# Banks_13_14.net
KiCad netlist of a schematic drawn in Altium Designer
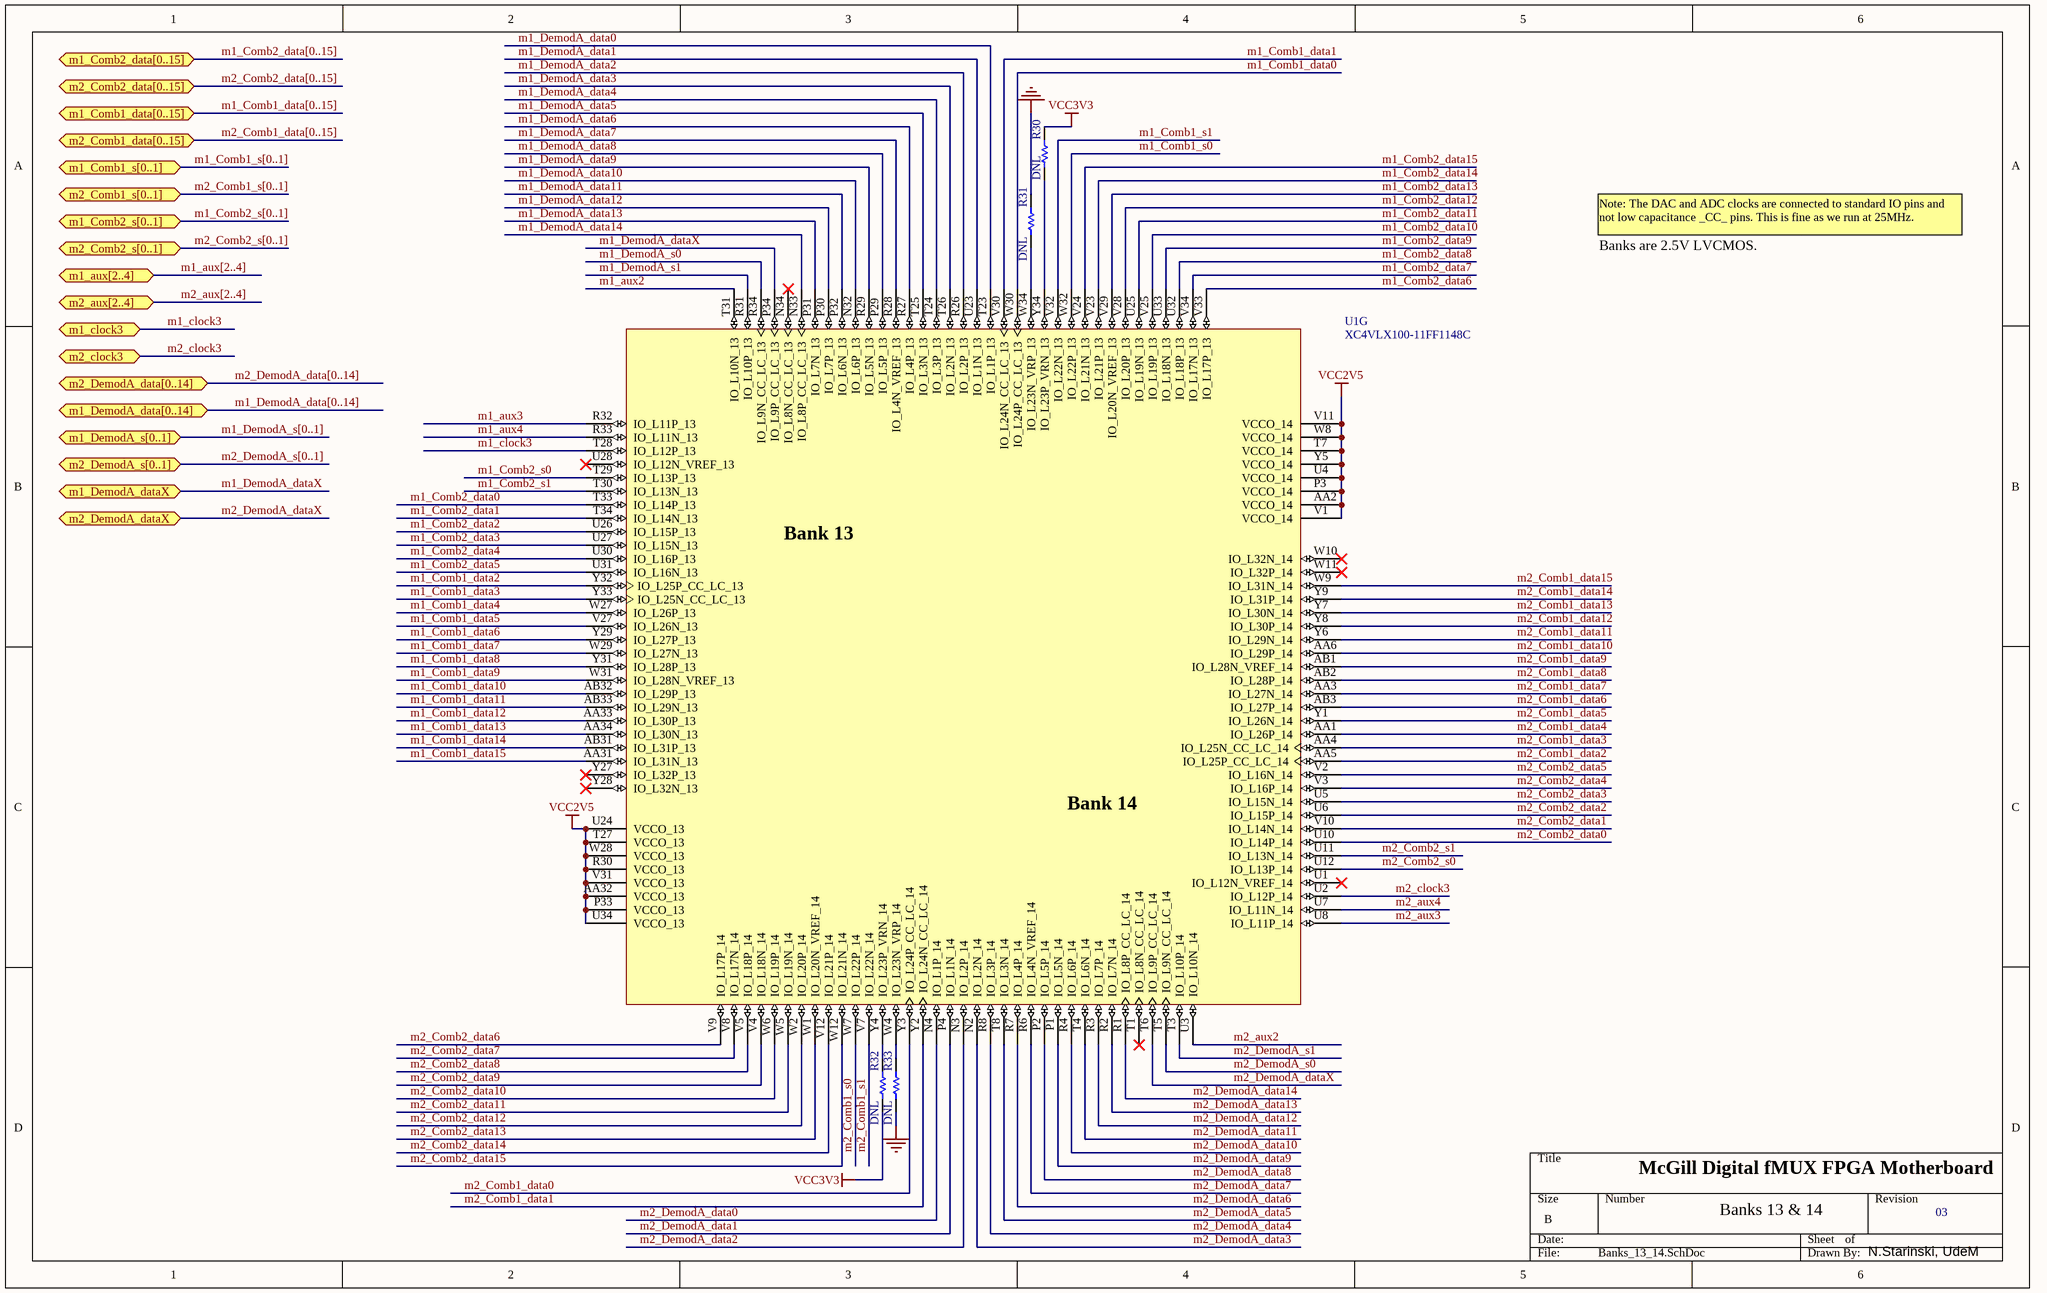
[diagram p0: Banks_13_14.SchDoc]

(export (version "E")
  (design (tool "Eeschema 10.0.6"))
  (components
    (comp (ref "R30")
      (value "DNL")
      (footprint "CR1608-0603")
      (description "Semiconductor Resistor")
      (fields (field (name "PUBLISHER") "Altium Limited"))
      (libsource (lib "Miscellaneous Devices") (part "Res Semi"))
    )
    (comp (ref "R31")
      (value "DNL")
      (footprint "CR1608-0603")
      (description "Semiconductor Resistor")
      (fields (field (name "PUBLISHER") "Altium Limited"))
      (libsource (lib "Miscellaneous Devices") (part "Res Semi"))
    )
    (comp (ref "R32")
      (value "DNL")
      (footprint "CR1608-0603")
      (description "Semiconductor Resistor")
      (fields (field (name "PUBLISHER") "Altium Limited"))
      (libsource (lib "Miscellaneous Devices") (part "Res Semi"))
    )
    (comp (ref "R33")
      (value "DNL")
      (footprint "CR1608-0603")
      (description "Semiconductor Resistor")
      (fields (field (name "PUBLISHER") "Altium Limited"))
      (libsource (lib "Miscellaneous Devices") (part "Res Semi"))
    )
    (comp (ref "U1")
      (value "XC4VLX100-11FF1148C")
      (footprint "FF1148")
      (description "Xilinx Virtex-4 LX Platform FPGA, 1148-Ball FFBGA, Speed Grade 11, 768 User I/Os, Commercial Grade")
      (fields (field (name "PUBLISHER") "Altium Limited"))
      (libsource (lib "Xilinx Virtex-4") (part "XC4VLX100-11FF1148C"))
    )
  )
  (nets
    (net (code "1") (name "/m1_Comb1_data0") (class "Default")
      (node (ref "U1") (pin "W30") (pinfunction "IO_L24P_CC_LC_13_W30") (pintype "bidirectional"))
    )
    (net (code "2") (name "/m1_Comb1_data1") (class "Default")
      (node (ref "U1") (pin "V30") (pinfunction "IO_L24N_CC_LC_13_V30") (pintype "bidirectional"))
    )
    (net (code "3") (name "/m1_Comb1_data2") (class "Default")
      (node (ref "U1") (pin "Y32") (pinfunction "IO_L25P_CC_LC_13_Y32") (pintype "bidirectional"))
    )
    (net (code "4") (name "/m1_Comb1_data3") (class "Default")
      (node (ref "U1") (pin "Y33") (pinfunction "IO_L25N_CC_LC_13_Y33") (pintype "bidirectional"))
    )
    (net (code "5") (name "/m1_Comb1_data4") (class "Default")
      (node (ref "U1") (pin "W27") (pinfunction "IO_L26P_13_W27") (pintype "bidirectional"))
    )
    (net (code "6") (name "/m1_Comb1_data5") (class "Default")
      (node (ref "U1") (pin "V27") (pinfunction "IO_L26N_13_V27") (pintype "bidirectional"))
    )
    (net (code "7") (name "/m1_Comb1_data6") (class "Default")
      (node (ref "U1") (pin "Y29") (pinfunction "IO_L27P_13_Y29") (pintype "bidirectional"))
    )
    (net (code "8") (name "/m1_Comb1_data7") (class "Default")
      (node (ref "U1") (pin "W29") (pinfunction "IO_L27N_13_W29") (pintype "bidirectional"))
    )
    (net (code "9") (name "/m1_Comb1_data8") (class "Default")
      (node (ref "U1") (pin "Y31") (pinfunction "IO_L28P_13_Y31") (pintype "bidirectional"))
    )
    (net (code "10") (name "/m1_Comb1_data9") (class "Default")
      (node (ref "U1") (pin "W31") (pinfunction "IO_L28N_VREF_13_W31") (pintype "bidirectional"))
    )
    (net (code "11") (name "/m1_Comb1_data10") (class "Default")
      (node (ref "U1") (pin "AB32") (pinfunction "IO_L29P_13_AB32") (pintype "bidirectional"))
    )
    (net (code "12") (name "/m1_Comb1_data11") (class "Default")
      (node (ref "U1") (pin "AB33") (pinfunction "IO_L29N_13_AB33") (pintype "bidirectional"))
    )
    (net (code "13") (name "/m1_Comb1_data12") (class "Default")
      (node (ref "U1") (pin "AA33") (pinfunction "IO_L30P_13_AA33") (pintype "bidirectional"))
    )
    (net (code "14") (name "/m1_Comb1_data13") (class "Default")
      (node (ref "U1") (pin "AA34") (pinfunction "IO_L30N_13_AA34") (pintype "bidirectional"))
    )
    (net (code "15") (name "/m1_Comb1_data14") (class "Default")
      (node (ref "U1") (pin "AB31") (pinfunction "IO_L31P_13_AB31") (pintype "bidirectional"))
    )
    (net (code "16") (name "/m1_Comb1_data15") (class "Default")
      (node (ref "U1") (pin "AA31") (pinfunction "IO_L31N_13_AA31") (pintype "bidirectional"))
    )
    (net (code "18") (name "/m1_Comb1_s0") (class "Default")
      (node (ref "U1") (pin "W32") (pinfunction "IO_L22P_13_W32") (pintype "bidirectional"))
    )
    (net (code "19") (name "/m1_Comb1_s1") (class "Default")
      (node (ref "U1") (pin "V32") (pinfunction "IO_L22N_13_V32") (pintype "bidirectional"))
    )
    (net (code "21") (name "/m1_Comb2_data0") (class "Default")
      (node (ref "U1") (pin "T33") (pinfunction "IO_L14P_13_T33") (pintype "bidirectional"))
    )
    (net (code "22") (name "/m1_Comb2_data1") (class "Default")
      (node (ref "U1") (pin "T34") (pinfunction "IO_L14N_13_T34") (pintype "bidirectional"))
    )
    (net (code "23") (name "/m1_Comb2_data2") (class "Default")
      (node (ref "U1") (pin "U26") (pinfunction "IO_L15P_13_U26") (pintype "bidirectional"))
    )
    (net (code "24") (name "/m1_Comb2_data3") (class "Default")
      (node (ref "U1") (pin "U27") (pinfunction "IO_L15N_13_U27") (pintype "bidirectional"))
    )
    (net (code "25") (name "/m1_Comb2_data4") (class "Default")
      (node (ref "U1") (pin "U30") (pinfunction "IO_L16P_13_U30") (pintype "bidirectional"))
    )
    (net (code "26") (name "/m1_Comb2_data5") (class "Default")
      (node (ref "U1") (pin "U31") (pinfunction "IO_L16N_13_U31") (pintype "bidirectional"))
    )
    (net (code "27") (name "/m1_Comb2_data6") (class "Default")
      (node (ref "U1") (pin "V33") (pinfunction "IO_L17P_13_V33") (pintype "bidirectional"))
    )
    (net (code "28") (name "/m1_Comb2_data7") (class "Default")
      (node (ref "U1") (pin "V34") (pinfunction "IO_L17N_13_V34") (pintype "bidirectional"))
    )
    (net (code "29") (name "/m1_Comb2_data8") (class "Default")
      (node (ref "U1") (pin "U32") (pinfunction "IO_L18P_13_U32") (pintype "bidirectional"))
    )
    (net (code "30") (name "/m1_Comb2_data9") (class "Default")
      (node (ref "U1") (pin "U33") (pinfunction "IO_L18N_13_U33") (pintype "bidirectional"))
    )
    (net (code "31") (name "/m1_Comb2_data10") (class "Default")
      (node (ref "U1") (pin "V25") (pinfunction "IO_L19P_13_V25") (pintype "bidirectional"))
    )
    (net (code "32") (name "/m1_Comb2_data11") (class "Default")
      (node (ref "U1") (pin "U25") (pinfunction "IO_L19N_13_U25") (pintype "bidirectional"))
    )
    (net (code "33") (name "/m1_Comb2_data12") (class "Default")
      (node (ref "U1") (pin "V28") (pinfunction "IO_L20P_13_V28") (pintype "bidirectional"))
    )
    (net (code "34") (name "/m1_Comb2_data13") (class "Default")
      (node (ref "U1") (pin "V29") (pinfunction "IO_L20N_VREF_13_V29") (pintype "bidirectional"))
    )
    (net (code "35") (name "/m1_Comb2_data14") (class "Default")
      (node (ref "U1") (pin "V23") (pinfunction "IO_L21P_13_V23") (pintype "bidirectional"))
    )
    (net (code "36") (name "/m1_Comb2_data15") (class "Default")
      (node (ref "U1") (pin "V24") (pinfunction "IO_L21N_13_V24") (pintype "bidirectional"))
    )
    (net (code "38") (name "/m1_Comb2_s0") (class "Default")
      (node (ref "U1") (pin "T29") (pinfunction "IO_L13P_13_T29") (pintype "bidirectional"))
    )
    (net (code "39") (name "/m1_Comb2_s1") (class "Default")
      (node (ref "U1") (pin "T30") (pinfunction "IO_L13N_13_T30") (pintype "bidirectional"))
    )
    (net (code "41") (name "/m1_DemodA_data0") (class "Default")
      (node (ref "U1") (pin "T23") (pinfunction "IO_L1P_13_T23") (pintype "bidirectional"))
    )
    (net (code "42") (name "/m1_DemodA_data1") (class "Default")
      (node (ref "U1") (pin "U23") (pinfunction "IO_L1N_13_U23") (pintype "bidirectional"))
    )
    (net (code "43") (name "/m1_DemodA_data2") (class "Default")
      (node (ref "U1") (pin "R26") (pinfunction "IO_L2P_13_R26") (pintype "bidirectional"))
    )
    (net (code "44") (name "/m1_DemodA_data3") (class "Default")
      (node (ref "U1") (pin "T26") (pinfunction "IO_L2N_13_T26") (pintype "bidirectional"))
    )
    (net (code "45") (name "/m1_DemodA_data4") (class "Default")
      (node (ref "U1") (pin "T24") (pinfunction "IO_L3P_13_T24") (pintype "bidirectional"))
    )
    (net (code "46") (name "/m1_DemodA_data5") (class "Default")
      (node (ref "U1") (pin "T25") (pinfunction "IO_L3N_13_T25") (pintype "bidirectional"))
    )
    (net (code "47") (name "/m1_DemodA_data6") (class "Default")
      (node (ref "U1") (pin "R27") (pinfunction "IO_L4P_13_R27") (pintype "bidirectional"))
    )
    (net (code "48") (name "/m1_DemodA_data7") (class "Default")
      (node (ref "U1") (pin "R28") (pinfunction "IO_L4N_VREF_13_R28") (pintype "bidirectional"))
    )
    (net (code "49") (name "/m1_DemodA_data8") (class "Default")
      (node (ref "U1") (pin "P29") (pinfunction "IO_L5P_13_P29") (pintype "bidirectional"))
    )
    (net (code "50") (name "/m1_DemodA_data9") (class "Default")
      (node (ref "U1") (pin "R29") (pinfunction "IO_L5N_13_R29") (pintype "bidirectional"))
    )
    (net (code "51") (name "/m1_DemodA_data10") (class "Default")
      (node (ref "U1") (pin "N32") (pinfunction "IO_L6P_13_N32") (pintype "bidirectional"))
    )
    (net (code "52") (name "/m1_DemodA_data11") (class "Default")
      (node (ref "U1") (pin "P32") (pinfunction "IO_L6N_13_P32") (pintype "bidirectional"))
    )
    (net (code "53") (name "/m1_DemodA_data12") (class "Default")
      (node (ref "U1") (pin "P30") (pinfunction "IO_L7P_13_P30") (pintype "bidirectional"))
    )
    (net (code "54") (name "/m1_DemodA_data13") (class "Default")
      (node (ref "U1") (pin "P31") (pinfunction "IO_L7N_13_P31") (pintype "bidirectional"))
    )
    (net (code "55") (name "/m1_DemodA_data14") (class "Default")
      (node (ref "U1") (pin "N33") (pinfunction "IO_L8P_CC_LC_13_N33") (pintype "bidirectional"))
    )
    (net (code "56") (name "/m1_DemodA_dataX") (class "Default")
      (node (ref "U1") (pin "P34") (pinfunction "IO_L9P_CC_LC_13_P34") (pintype "bidirectional"))
    )
    (net (code "58") (name "/m1_DemodA_s0") (class "Default")
      (node (ref "U1") (pin "R34") (pinfunction "IO_L9N_CC_LC_13_R34") (pintype "bidirectional"))
    )
    (net (code "59") (name "/m1_DemodA_s1") (class "Default")
      (node (ref "U1") (pin "R31") (pinfunction "IO_L10P_13_R31") (pintype "bidirectional"))
    )
    (net (code "61") (name "/m1_aux2") (class "Default")
      (node (ref "U1") (pin "T31") (pinfunction "IO_L10N_13_T31") (pintype "bidirectional"))
    )
    (net (code "62") (name "/m1_aux3") (class "Default")
      (node (ref "U1") (pin "R32") (pinfunction "IO_L11P_13_R32") (pintype "bidirectional"))
    )
    (net (code "63") (name "/m1_aux4") (class "Default")
      (node (ref "U1") (pin "R33") (pinfunction "IO_L11N_13_R33") (pintype "bidirectional"))
    )
    (net (code "65") (name "/m1_clock3") (class "Default")
      (node (ref "U1") (pin "T28") (pinfunction "IO_L12P_13_T28") (pintype "bidirectional"))
    )
    (net (code "66") (name "/m2_Comb1_data0") (class "Default")
      (node (ref "U1") (pin "Y3") (pinfunction "IO_L24P_CC_LC_14_Y3") (pintype "bidirectional"))
    )
    (net (code "67") (name "/m2_Comb1_data1") (class "Default")
      (node (ref "U1") (pin "Y2") (pinfunction "IO_L24N_CC_LC_14_Y2") (pintype "bidirectional"))
    )
    (net (code "68") (name "/m2_Comb1_data2") (class "Default")
      (node (ref "U1") (pin "AA5") (pinfunction "IO_L25P_CC_LC_14_AA5") (pintype "bidirectional"))
    )
    (net (code "69") (name "/m2_Comb1_data3") (class "Default")
      (node (ref "U1") (pin "AA4") (pinfunction "IO_L25N_CC_LC_14_AA4") (pintype "bidirectional"))
    )
    (net (code "70") (name "/m2_Comb1_data4") (class "Default")
      (node (ref "U1") (pin "AA1") (pinfunction "IO_L26P_14_AA1") (pintype "bidirectional"))
    )
    (net (code "71") (name "/m2_Comb1_data5") (class "Default")
      (node (ref "U1") (pin "Y1") (pinfunction "IO_L26N_14_Y1") (pintype "bidirectional"))
    )
    (net (code "72") (name "/m2_Comb1_data6") (class "Default")
      (node (ref "U1") (pin "AB3") (pinfunction "IO_L27P_14_AB3") (pintype "bidirectional"))
    )
    (net (code "73") (name "/m2_Comb1_data7") (class "Default")
      (node (ref "U1") (pin "AA3") (pinfunction "IO_L27N_14_AA3") (pintype "bidirectional"))
    )
    (net (code "74") (name "/m2_Comb1_data8") (class "Default")
      (node (ref "U1") (pin "AB2") (pinfunction "IO_L28P_14_AB2") (pintype "bidirectional"))
    )
    (net (code "75") (name "/m2_Comb1_data9") (class "Default")
      (node (ref "U1") (pin "AB1") (pinfunction "IO_L28N_VREF_14_AB1") (pintype "bidirectional"))
    )
    (net (code "76") (name "/m2_Comb1_data10") (class "Default")
      (node (ref "U1") (pin "AA6") (pinfunction "IO_L29P_14_AA6") (pintype "bidirectional"))
    )
    (net (code "77") (name "/m2_Comb1_data11") (class "Default")
      (node (ref "U1") (pin "Y6") (pinfunction "IO_L29N_14_Y6") (pintype "bidirectional"))
    )
    (net (code "78") (name "/m2_Comb1_data12") (class "Default")
      (node (ref "U1") (pin "Y8") (pinfunction "IO_L30P_14_Y8") (pintype "bidirectional"))
    )
    (net (code "79") (name "/m2_Comb1_data13") (class "Default")
      (node (ref "U1") (pin "Y7") (pinfunction "IO_L30N_14_Y7") (pintype "bidirectional"))
    )
    (net (code "80") (name "/m2_Comb1_data14") (class "Default")
      (node (ref "U1") (pin "Y9") (pinfunction "IO_L31P_14_Y9") (pintype "bidirectional"))
    )
    (net (code "81") (name "/m2_Comb1_data15") (class "Default")
      (node (ref "U1") (pin "W9") (pinfunction "IO_L31N_14_W9") (pintype "bidirectional"))
    )
    (net (code "83") (name "/m2_Comb1_s0") (class "Default")
      (node (ref "U1") (pin "W7") (pinfunction "IO_L22P_14_W7") (pintype "bidirectional"))
    )
    (net (code "84") (name "/m2_Comb1_s1") (class "Default")
      (node (ref "U1") (pin "V7") (pinfunction "IO_L22N_14_V7") (pintype "bidirectional"))
    )
    (net (code "86") (name "/m2_Comb2_data0") (class "Default")
      (node (ref "U1") (pin "U10") (pinfunction "IO_L14P_14_U10") (pintype "bidirectional"))
    )
    (net (code "87") (name "/m2_Comb2_data1") (class "Default")
      (node (ref "U1") (pin "V10") (pinfunction "IO_L14N_14_V10") (pintype "bidirectional"))
    )
    (net (code "88") (name "/m2_Comb2_data2") (class "Default")
      (node (ref "U1") (pin "U6") (pinfunction "IO_L15P_14_U6") (pintype "bidirectional"))
    )
    (net (code "89") (name "/m2_Comb2_data3") (class "Default")
      (node (ref "U1") (pin "U5") (pinfunction "IO_L15N_14_U5") (pintype "bidirectional"))
    )
    (net (code "90") (name "/m2_Comb2_data4") (class "Default")
      (node (ref "U1") (pin "V3") (pinfunction "IO_L16P_14_V3") (pintype "bidirectional"))
    )
    (net (code "91") (name "/m2_Comb2_data5") (class "Default")
      (node (ref "U1") (pin "V2") (pinfunction "IO_L16N_14_V2") (pintype "bidirectional"))
    )
    (net (code "92") (name "/m2_Comb2_data6") (class "Default")
      (node (ref "U1") (pin "V9") (pinfunction "IO_L17P_14_V9") (pintype "bidirectional"))
    )
    (net (code "93") (name "/m2_Comb2_data7") (class "Default")
      (node (ref "U1") (pin "V8") (pinfunction "IO_L17N_14_V8") (pintype "bidirectional"))
    )
    (net (code "94") (name "/m2_Comb2_data8") (class "Default")
      (node (ref "U1") (pin "V5") (pinfunction "IO_L18P_14_V5") (pintype "bidirectional"))
    )
    (net (code "95") (name "/m2_Comb2_data9") (class "Default")
      (node (ref "U1") (pin "V4") (pinfunction "IO_L18N_14_V4") (pintype "bidirectional"))
    )
    (net (code "96") (name "/m2_Comb2_data10") (class "Default")
      (node (ref "U1") (pin "W6") (pinfunction "IO_L19P_14_W6") (pintype "bidirectional"))
    )
    (net (code "97") (name "/m2_Comb2_data11") (class "Default")
      (node (ref "U1") (pin "W5") (pinfunction "IO_L19N_14_W5") (pintype "bidirectional"))
    )
    (net (code "98") (name "/m2_Comb2_data12") (class "Default")
      (node (ref "U1") (pin "W2") (pinfunction "IO_L20P_14_W2") (pintype "bidirectional"))
    )
    (net (code "99") (name "/m2_Comb2_data13") (class "Default")
      (node (ref "U1") (pin "W1") (pinfunction "IO_L20N_VREF_14_W1") (pintype "bidirectional"))
    )
    (net (code "100") (name "/m2_Comb2_data14") (class "Default")
      (node (ref "U1") (pin "V12") (pinfunction "IO_L21P_14_V12") (pintype "bidirectional"))
    )
    (net (code "101") (name "/m2_Comb2_data15") (class "Default")
      (node (ref "U1") (pin "W12") (pinfunction "IO_L21N_14_W12") (pintype "bidirectional"))
    )
    (net (code "103") (name "/m2_Comb2_s0") (class "Default")
      (node (ref "U1") (pin "U12") (pinfunction "IO_L13P_14_U12") (pintype "bidirectional"))
    )
    (net (code "104") (name "/m2_Comb2_s1") (class "Default")
      (node (ref "U1") (pin "U11") (pinfunction "IO_L13N_14_U11") (pintype "bidirectional"))
    )
    (net (code "106") (name "/m2_DemodA_data0") (class "Default")
      (node (ref "U1") (pin "N4") (pinfunction "IO_L1P_14_N4") (pintype "bidirectional"))
    )
    (net (code "107") (name "/m2_DemodA_data1") (class "Default")
      (node (ref "U1") (pin "P4") (pinfunction "IO_L1N_14_P4") (pintype "bidirectional"))
    )
    (net (code "108") (name "/m2_DemodA_data2") (class "Default")
      (node (ref "U1") (pin "N3") (pinfunction "IO_L2P_14_N3") (pintype "bidirectional"))
    )
    (net (code "109") (name "/m2_DemodA_data3") (class "Default")
      (node (ref "U1") (pin "N2") (pinfunction "IO_L2N_14_N2") (pintype "bidirectional"))
    )
    (net (code "110") (name "/m2_DemodA_data4") (class "Default")
      (node (ref "U1") (pin "R8") (pinfunction "IO_L3P_14_R8") (pintype "bidirectional"))
    )
    (net (code "111") (name "/m2_DemodA_data5") (class "Default")
      (node (ref "U1") (pin "T8") (pinfunction "IO_L3N_14_T8") (pintype "bidirectional"))
    )
    (net (code "112") (name "/m2_DemodA_data6") (class "Default")
      (node (ref "U1") (pin "R7") (pinfunction "IO_L4P_14_R7") (pintype "bidirectional"))
    )
    (net (code "113") (name "/m2_DemodA_data7") (class "Default")
      (node (ref "U1") (pin "R6") (pinfunction "IO_L4N_VREF_14_R6") (pintype "bidirectional"))
    )
    (net (code "114") (name "/m2_DemodA_data8") (class "Default")
      (node (ref "U1") (pin "P2") (pinfunction "IO_L5P_14_P2") (pintype "bidirectional"))
    )
    (net (code "115") (name "/m2_DemodA_data9") (class "Default")
      (node (ref "U1") (pin "P1") (pinfunction "IO_L5N_14_P1") (pintype "bidirectional"))
    )
    (net (code "116") (name "/m2_DemodA_data10") (class "Default")
      (node (ref "U1") (pin "R4") (pinfunction "IO_L6P_14_R4") (pintype "bidirectional"))
    )
    (net (code "117") (name "/m2_DemodA_data11") (class "Default")
      (node (ref "U1") (pin "T4") (pinfunction "IO_L6N_14_T4") (pintype "bidirectional"))
    )
    (net (code "118") (name "/m2_DemodA_data12") (class "Default")
      (node (ref "U1") (pin "R3") (pinfunction "IO_L7P_14_R3") (pintype "bidirectional"))
    )
    (net (code "119") (name "/m2_DemodA_data13") (class "Default")
      (node (ref "U1") (pin "R2") (pinfunction "IO_L7N_14_R2") (pintype "bidirectional"))
    )
    (net (code "120") (name "/m2_DemodA_data14") (class "Default")
      (node (ref "U1") (pin "R1") (pinfunction "IO_L8P_CC_LC_14_R1") (pintype "bidirectional"))
    )
    (net (code "121") (name "/m2_DemodA_dataX") (class "Default")
      (node (ref "U1") (pin "T6") (pinfunction "IO_L9P_CC_LC_14_T6") (pintype "bidirectional"))
    )
    (net (code "123") (name "/m2_DemodA_s0") (class "Default")
      (node (ref "U1") (pin "T5") (pinfunction "IO_L9N_CC_LC_14_T5") (pintype "bidirectional"))
    )
    (net (code "124") (name "/m2_DemodA_s1") (class "Default")
      (node (ref "U1") (pin "T3") (pinfunction "IO_L10P_14_T3") (pintype "bidirectional"))
    )
    (net (code "126") (name "/m2_aux2") (class "Default")
      (node (ref "U1") (pin "U3") (pinfunction "IO_L10N_14_U3") (pintype "bidirectional"))
    )
    (net (code "127") (name "/m2_aux3") (class "Default")
      (node (ref "U1") (pin "U8") (pinfunction "IO_L11P_14_U8") (pintype "bidirectional"))
    )
    (net (code "128") (name "/m2_aux4") (class "Default")
      (node (ref "U1") (pin "U7") (pinfunction "IO_L11N_14_U7") (pintype "bidirectional"))
    )
    (net (code "130") (name "/m2_clock3") (class "Default")
      (node (ref "U1") (pin "U2") (pinfunction "IO_L12P_14_U2") (pintype "bidirectional"))
    )
    (net (code "131") (name "GND") (class "Default")
      (node (ref "R31") (pin "2") (pinfunction "2_2") (pintype "passive"))
      (node (ref "R33") (pin "1") (pinfunction "1_1") (pintype "passive"))
    )
    (net (code "132") (name "Net-(U1G-IO_L23N_VRP_13)") (class "Default")
      (node (ref "R31") (pin "1") (pinfunction "1_1") (pintype "passive"))
      (node (ref "U1") (pin "W34") (pinfunction "IO_L23N_VRP_13_W34") (pintype "bidirectional"))
    )
    (net (code "133") (name "Net-(U1G-IO_L23N_VRP_14)") (class "Default")
      (node (ref "R33") (pin "2") (pinfunction "2_2") (pintype "passive"))
      (node (ref "U1") (pin "W4") (pinfunction "IO_L23N_VRP_14_W4") (pintype "bidirectional"))
    )
    (net (code "134") (name "Net-(U1G-IO_L23P_VRN_13)") (class "Default")
      (node (ref "R30") (pin "1") (pinfunction "1_1") (pintype "passive"))
      (node (ref "U1") (pin "Y34") (pinfunction "IO_L23P_VRN_13_Y34") (pintype "bidirectional"))
    )
    (net (code "135") (name "Net-(U1G-IO_L23P_VRN_14)") (class "Default")
      (node (ref "R32") (pin "2") (pinfunction "2_2") (pintype "passive"))
      (node (ref "U1") (pin "Y4") (pinfunction "IO_L23P_VRN_14_Y4") (pintype "bidirectional"))
    )
    (net (code "136") (name "VCC2V5") (class "Default")
      (node (ref "U1") (pin "AA2") (pinfunction "VCCO_14_AA2") (pintype "power_in"))
      (node (ref "U1") (pin "AA32") (pinfunction "VCCO_13_AA32") (pintype "power_in"))
      (node (ref "U1") (pin "P3") (pinfunction "VCCO_14_P3") (pintype "power_in"))
      (node (ref "U1") (pin "P33") (pinfunction "VCCO_13_P33") (pintype "power_in"))
      (node (ref "U1") (pin "R30") (pinfunction "VCCO_13_R30") (pintype "power_in"))
      (node (ref "U1") (pin "T27") (pinfunction "VCCO_13_T27") (pintype "power_in"))
      (node (ref "U1") (pin "T7") (pinfunction "VCCO_14_T7") (pintype "power_in"))
      (node (ref "U1") (pin "U24") (pinfunction "VCCO_13_U24") (pintype "power_in"))
      (node (ref "U1") (pin "U34") (pinfunction "VCCO_13_U34") (pintype "power_in"))
      (node (ref "U1") (pin "U4") (pinfunction "VCCO_14_U4") (pintype "power_in"))
      (node (ref "U1") (pin "V1") (pinfunction "VCCO_14_V1") (pintype "power_in"))
      (node (ref "U1") (pin "V11") (pinfunction "VCCO_14_V11") (pintype "power_in"))
      (node (ref "U1") (pin "V31") (pinfunction "VCCO_13_V31") (pintype "power_in"))
      (node (ref "U1") (pin "W28") (pinfunction "VCCO_13_W28") (pintype "power_in"))
      (node (ref "U1") (pin "W8") (pinfunction "VCCO_14_W8") (pintype "power_in"))
      (node (ref "U1") (pin "Y5") (pinfunction "VCCO_14_Y5") (pintype "power_in"))
    )
    (net (code "137") (name "VCC3V3") (class "Default")
      (node (ref "R30") (pin "2") (pinfunction "2_2") (pintype "passive"))
      (node (ref "R32") (pin "1") (pinfunction "1_1") (pintype "passive"))
    )
    (net (code "138") (name "unconnected-(U1G-IO_L8N_CC_LC_13-PadN34)") (class "Default")
      (node (ref "U1") (pin "N34") (pinfunction "IO_L8N_CC_LC_13_N34") (pintype "bidirectional+no_connect"))
    )
    (net (code "139") (name "unconnected-(U1G-IO_L8N_CC_LC_14-PadT1)") (class "Default")
      (node (ref "U1") (pin "T1") (pinfunction "IO_L8N_CC_LC_14_T1") (pintype "bidirectional+no_connect"))
    )
    (net (code "140") (name "unconnected-(U1G-IO_L12N_VREF_13-PadU28)") (class "Default")
      (node (ref "U1") (pin "U28") (pinfunction "IO_L12N_VREF_13_U28") (pintype "bidirectional+no_connect"))
    )
    (net (code "141") (name "unconnected-(U1G-IO_L12N_VREF_14-PadU1)") (class "Default")
      (node (ref "U1") (pin "U1") (pinfunction "IO_L12N_VREF_14_U1") (pintype "bidirectional+no_connect"))
    )
    (net (code "142") (name "unconnected-(U1G-IO_L32N_13-PadY28)") (class "Default")
      (node (ref "U1") (pin "Y28") (pinfunction "IO_L32N_13_Y28") (pintype "bidirectional+no_connect"))
    )
    (net (code "143") (name "unconnected-(U1G-IO_L32N_14-PadW10)") (class "Default")
      (node (ref "U1") (pin "W10") (pinfunction "IO_L32N_14_W10") (pintype "bidirectional+no_connect"))
    )
    (net (code "144") (name "unconnected-(U1G-IO_L32P_13-PadY27)") (class "Default")
      (node (ref "U1") (pin "Y27") (pinfunction "IO_L32P_13_Y27") (pintype "bidirectional+no_connect"))
    )
    (net (code "145") (name "unconnected-(U1G-IO_L32P_14-PadW11)") (class "Default")
      (node (ref "U1") (pin "W11") (pinfunction "IO_L32P_14_W11") (pintype "bidirectional+no_connect"))
    )
  )
)
